# PowerManager.net
KiCad netlist of a schematic drawn in Altium Designer
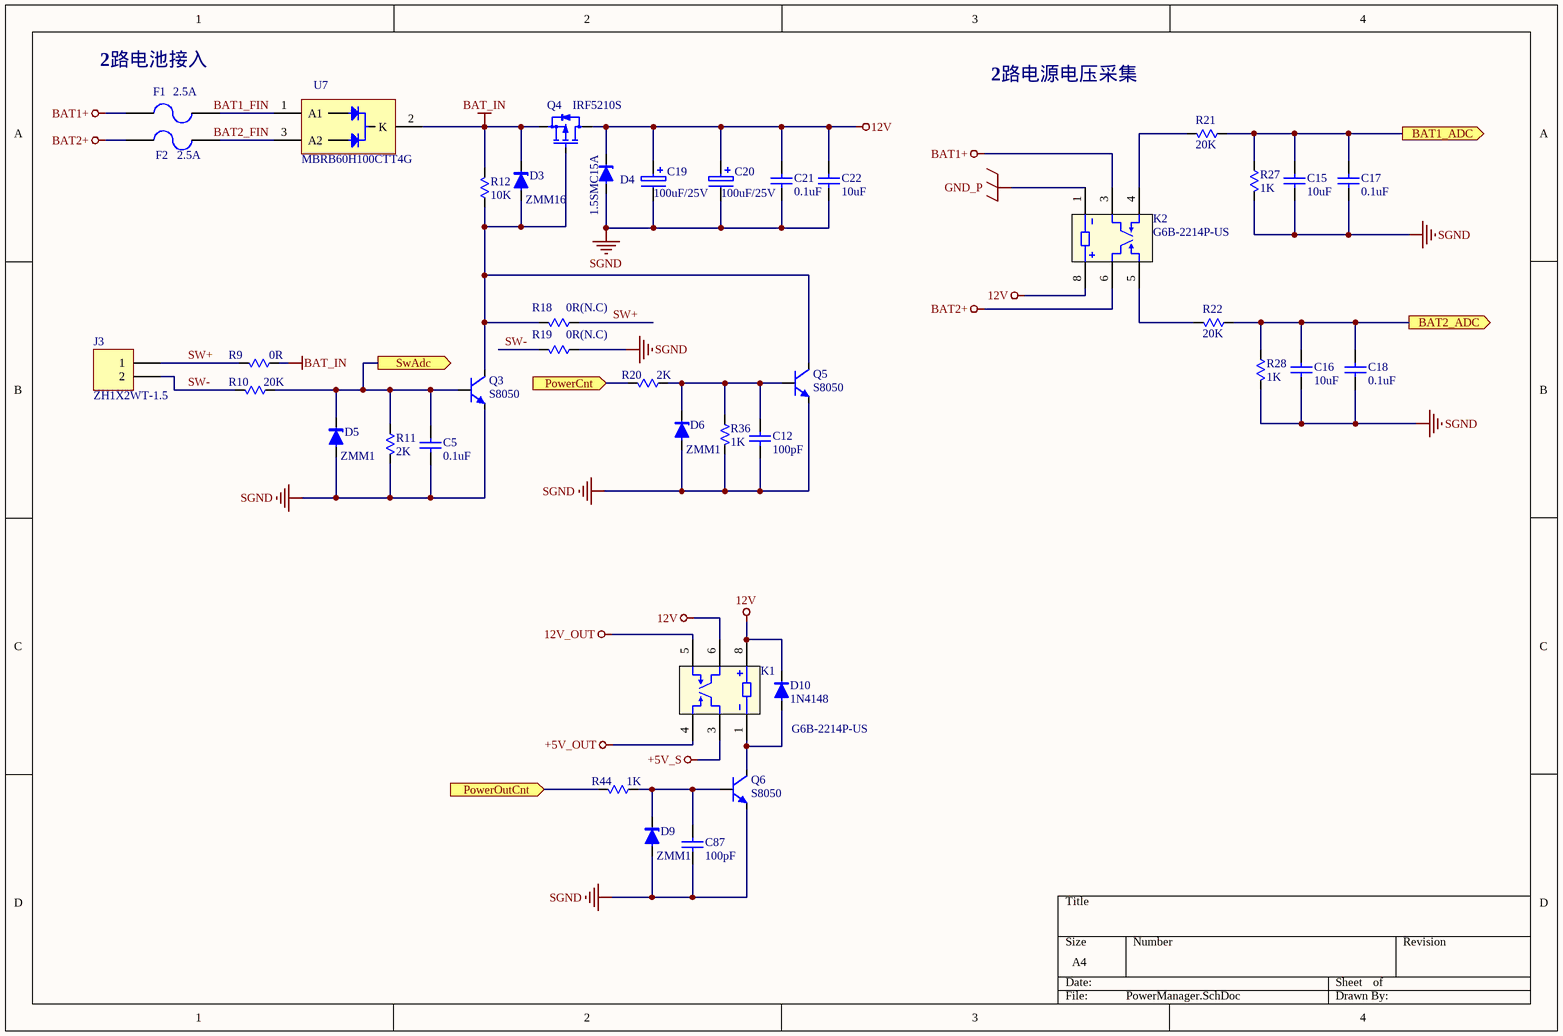
[diagram p0: PowerManager.SchDoc]

(export (version "E")
  (design (tool "Eeschema 10.0.6"))
  (components
    (comp (ref "C5")
      (value "0.1uF")
      (footprint "C0805")
      (description "Capacitor")
      (fields (field (name "PUBLISHER") "Altium Limited"))
      (libsource (lib "Miscellaneous Devices") (part "Cap"))
    )
    (comp (ref "C12")
      (value "100pF")
      (footprint "C0805")
      (description "Capacitor")
      (fields (field (name "PUBLISHER") "Altium Limited"))
      (libsource (lib "Miscellaneous Devices") (part "Cap"))
    )
    (comp (ref "C15")
      (value "10uF")
      (footprint "C0805")
      (description "CAP")
      (fields (field (name "PUBLISHER") "Altium Limited"))
      (libsource (lib "Passive Components Class") (part "CAP"))
    )
    (comp (ref "C16")
      (value "10uF")
      (footprint "C0805")
      (description "CAP")
      (fields (field (name "PUBLISHER") "Altium Limited"))
      (libsource (lib "Passive Components Class") (part "CAP"))
    )
    (comp (ref "C17")
      (value "0.1uF")
      (footprint "C0805")
      (description "CAP")
      (fields (field (name "PUBLISHER") "Altium Limited"))
      (libsource (lib "Passive Components Class") (part "CAP"))
    )
    (comp (ref "C18")
      (value "0.1uF")
      (footprint "C0805")
      (description "CAP")
      (fields (field (name "PUBLISHER") "Altium Limited"))
      (libsource (lib "Passive Components Class") (part "CAP"))
    )
    (comp (ref "C19")
      (value "100uF/25V")
      (footprint "CT7343-E-S")
      (description "Electrolytic Capacitor")
      (libsource (lib "*") (part "ELECTRO"))
    )
    (comp (ref "C20")
      (value "100uF/25V")
      (footprint "CT7343-E-S")
      (description "Electrolytic Capacitor")
      (libsource (lib "*") (part "ELECTRO"))
    )
    (comp (ref "C21")
      (value "0.1uF")
      (footprint "C0805")
      (description "Capacitor")
      (fields (field (name "PUBLISHER") "Altium Limited"))
      (libsource (lib "Miscellaneous Devices") (part "Cap"))
    )
    (comp (ref "C22")
      (value "10uF")
      (footprint "C0805")
      (description "Capacitor")
      (fields (field (name "PUBLISHER") "Altium Limited"))
      (libsource (lib "Miscellaneous Devices") (part "Cap"))
    )
    (comp (ref "C87")
      (value "100pF")
      (footprint "C0805")
      (description "Capacitor")
      (fields (field (name "PUBLISHER") "Altium Limited"))
      (libsource (lib "Miscellaneous Devices") (part "Cap"))
    )
    (comp (ref "D3")
      (value "ZMM16")
      (footprint "SOD-80")
      (description "Small Signal Zener Diodes")
      (libsource (lib "Passive Components Class") (part "DIODE-ZENER"))
    )
    (comp (ref "D4")
      (value "1.5SMC15A")
      (footprint "SMC")
      (description "Small Signal Zener Diodes")
      (libsource (lib "Passive Components Class") (part "DIODE-ZENER"))
    )
    (comp (ref "D5")
      (value "ZMM1")
      (footprint "SOD-80")
      (description "Small Signal Zener Diodes")
      (libsource (lib "Passive Components Class") (part "DIODE-ZENER"))
    )
    (comp (ref "D6")
      (value "ZMM1")
      (footprint "SOD-80")
      (description "Small Signal Zener Diodes")
      (libsource (lib "Passive Components Class") (part "DIODE-ZENER"))
    )
    (comp (ref "D9")
      (value "ZMM1")
      (footprint "SOD-80")
      (description "Small Signal Zener Diodes")
      (libsource (lib "Passive Components Class") (part "DIODE-ZENER"))
    )
    (comp (ref "D10")
      (value "1N4148")
      (footprint "SOD-80")
      (description "Silicon Epitaxial Planar Diodes")
      (libsource (lib "Passive Components Class") (part "DIODE-SWITCHING"))
    )
    (comp (ref "F1")
      (value "2.5A")
      (footprint "F1812")
      (description "Fuse")
      (libsource (lib "*") (part "FUSE2"))
    )
    (comp (ref "F2")
      (value "2.5A")
      (footprint "F1812")
      (description "Fuse")
      (libsource (lib "*") (part "FUSE2"))
    )
    (comp (ref "J3")
      (value "ZH1X2WT-1.5")
      (footprint "ZH1X2WT-1.5")
      (description "Header, 2-Pin")
      (fields (field (name "PUBLISHER") "Altium Limited"))
      (libsource (lib "Miscellaneous Connectors") (part "Header 2"))
    )
    (comp (ref "K1")
      (value "G6B-2214P-US")
      (footprint "G6B-2214P-Us")
      (libsource (lib "Passive Components Class") (part "G6B-2214P-US"))
    )
    (comp (ref "K2")
      (value "G6B-2214P-US")
      (footprint "G6B-2214P-Us")
      (libsource (lib "") (part "G6B-2214P-US_1"))
    )
    (comp (ref "Q3")
      (value "S8050")
      (footprint "SOT-23")
      (description "NPN General Purpose Amplifier")
      (fields (field (name "PUBLISHER") "Altium Limited"))
      (libsource (lib "Bdmc4810") (part "NPN"))
    )
    (comp (ref "Q4")
      (value "IRF5210S")
      (footprint "TO-262")
      (description "P-Channel 30-V (D-S), 150 C MOSFET")
      (libsource (lib "Passive Components Class") (part "PMOS"))
    )
    (comp (ref "Q5")
      (value "S8050")
      (footprint "SOT-23")
      (description "NPN General Purpose Amplifier")
      (fields (field (name "PUBLISHER") "Altium Limited"))
      (libsource (lib "Bdmc4810") (part "NPN"))
    )
    (comp (ref "Q6")
      (value "S8050")
      (footprint "SOT-23")
      (description "NPN General Purpose Amplifier")
      (fields (field (name "PUBLISHER") "Altium Limited"))
      (libsource (lib "Bdmc4810") (part "NPN"))
    )
    (comp (ref "R9")
      (value "0R")
      (footprint "R0805")
      (description "Resistor")
      (fields (field (name "PUBLISHER") "Altium Limited"))
      (libsource (lib "Temp") (part "Res"))
    )
    (comp (ref "R10")
      (value "20K")
      (footprint "R0805")
      (description "Resistor")
      (fields (field (name "PUBLISHER") "Altium Limited"))
      (libsource (lib "Temp") (part "Res"))
    )
    (comp (ref "R11")
      (value "2K")
      (footprint "R0805")
      (description "Resistor")
      (fields (field (name "PUBLISHER") "Altium Limited"))
      (libsource (lib "Temp") (part "Res"))
    )
    (comp (ref "R12")
      (value "10K")
      (footprint "R0805")
      (description "Resistor")
      (fields (field (name "PUBLISHER") "Altium Limited"))
      (libsource (lib "Temp") (part "Res"))
    )
    (comp (ref "R18")
      (value "0R(N.C)")
      (footprint "R0805")
      (description "Resistor")
      (fields (field (name "PUBLISHER") "Altium Limited"))
      (libsource (lib "") (part "RES_1"))
    )
    (comp (ref "R19")
      (value "0R(N.C)")
      (footprint "R0805")
      (description "Resistor")
      (fields (field (name "PUBLISHER") "Altium Limited"))
      (libsource (lib "") (part "RES_1"))
    )
    (comp (ref "R20")
      (value "2K")
      (footprint "R0805")
      (description "Resistor")
      (fields (field (name "PUBLISHER") "Altium Limited"))
      (libsource (lib "Temp") (part "Res"))
    )
    (comp (ref "R21")
      (value "20K")
      (footprint "R0805")
      (description "Resistor")
      (fields (field (name "PUBLISHER") "Altium Limited"))
      (libsource (lib "Passive Components Class") (part "RES"))
    )
    (comp (ref "R22")
      (value "20K")
      (footprint "R0805")
      (description "Resistor")
      (fields (field (name "PUBLISHER") "Altium Limited"))
      (libsource (lib "Passive Components Class") (part "RES"))
    )
    (comp (ref "R27")
      (value "1K")
      (footprint "R0805")
      (description "Resistor")
      (fields (field (name "PUBLISHER") "Altium Limited"))
      (libsource (lib "Passive Components Class") (part "RES"))
    )
    (comp (ref "R28")
      (value "1K")
      (footprint "R0805")
      (description "Resistor")
      (fields (field (name "PUBLISHER") "Altium Limited"))
      (libsource (lib "Passive Components Class") (part "RES"))
    )
    (comp (ref "R36")
      (value "1K")
      (footprint "R0805")
      (description "Resistor")
      (fields (field (name "PUBLISHER") "Altium Limited"))
      (libsource (lib "Temp") (part "Res"))
    )
    (comp (ref "R44")
      (value "1K")
      (footprint "R0805")
      (description "Resistor")
      (fields (field (name "PUBLISHER") "Altium Limited"))
      (libsource (lib "Temp") (part "Res"))
    )
    (comp (ref "U7")
      (value "MBRB60H100CTT4G")
      (footprint "TO-262")
      (libsource (lib "Logic Class") (part "VB30200C"))
    )
  )
  (nets
    (net (code "1") (name "+5V_OUT") (class "Default")
      (node (ref "K1") (pin "4") (pinfunction "4_4") (pintype "passive"))
    )
    (net (code "2") (name "+5V_S") (class "Default")
      (node (ref "K1") (pin "3") (pinfunction "3_3") (pintype "passive"))
    )
    (net (code "3") (name "/BAT1_ADC") (class "Default")
      (node (ref "C15") (pin "1") (pinfunction "1_1") (pintype "passive"))
      (node (ref "C17") (pin "1") (pinfunction "1_1") (pintype "passive"))
      (node (ref "R21") (pin "2") (pinfunction "2_2") (pintype "passive"))
      (node (ref "R27") (pin "2") (pinfunction "2_2") (pintype "passive"))
    )
    (net (code "5") (name "/BAT2_ADC") (class "Default")
      (node (ref "C16") (pin "1") (pinfunction "1_1") (pintype "passive"))
      (node (ref "C18") (pin "1") (pinfunction "1_1") (pintype "passive"))
      (node (ref "R22") (pin "2") (pinfunction "2_2") (pintype "passive"))
      (node (ref "R28") (pin "2") (pinfunction "2_2") (pintype "passive"))
    )
    (net (code "7") (name "/PowerCnt") (class "Default")
      (node (ref "R20") (pin "1") (pinfunction "1_1") (pintype "passive"))
    )
    (net (code "8") (name "/PowerOutCnt") (class "Default")
      (node (ref "R44") (pin "1") (pinfunction "1_1") (pintype "passive"))
    )
    (net (code "9") (name "/SW+") (class "Default")
      (node (ref "J3") (pin "1") (pinfunction "1_1") (pintype "passive"))
      (node (ref "R18") (pin "1") (pinfunction "1_1") (pintype "passive"))
      (node (ref "R9") (pin "1") (pinfunction "1_1") (pintype "passive"))
    )
    (net (code "10") (name "/SW-") (class "Default")
      (node (ref "J3") (pin "2") (pinfunction "2_2") (pintype "passive"))
      (node (ref "R10") (pin "1") (pinfunction "1_1") (pintype "passive"))
      (node (ref "R19") (pin "2") (pinfunction "2_2") (pintype "passive"))
    )
    (net (code "11") (name "/SwAdc") (class "Default")
      (node (ref "C5") (pin "2") (pinfunction "2_2") (pintype "passive"))
      (node (ref "D5") (pin "2") (pinfunction "K_2") (pintype "passive"))
      (node (ref "Q3") (pin "1") (pinfunction "B_1") (pintype "passive"))
      (node (ref "R10") (pin "2") (pinfunction "2_2") (pintype "passive"))
      (node (ref "R11") (pin "2") (pinfunction "2_2") (pintype "passive"))
    )
    (net (code "12") (name "12V") (class "Default")
      (node (ref "C19") (pin "1") (pinfunction "1_1") (pintype "passive"))
      (node (ref "C20") (pin "1") (pinfunction "1_1") (pintype "passive"))
      (node (ref "C21") (pin "2") (pinfunction "2_2") (pintype "passive"))
      (node (ref "C22") (pin "2") (pinfunction "2_2") (pintype "passive"))
      (node (ref "D10") (pin "2") (pinfunction "K_2") (pintype "passive"))
      (node (ref "D4") (pin "2") (pinfunction "K_2") (pintype "passive"))
      (node (ref "K1") (pin "6") (pinfunction "6_6") (pintype "passive"))
      (node (ref "K1") (pin "8") (pinfunction "8_8") (pintype "passive"))
      (node (ref "K2") (pin "8") (pinfunction "8_8") (pintype "passive"))
      (node (ref "Q4") (pin "2") (pinfunction "D_2") (pintype "passive"))
    )
    (net (code "13") (name "12V_OUT") (class "Default")
      (node (ref "K1") (pin "5") (pinfunction "5_5") (pintype "passive"))
    )
    (net (code "14") (name "BAT1+") (class "Default")
      (node (ref "F1") (pin "1") (pinfunction "1_1") (pintype "passive"))
      (node (ref "K2") (pin "3") (pinfunction "3_3") (pintype "passive"))
    )
    (net (code "15") (name "BAT2+") (class "Default")
      (node (ref "F2") (pin "1") (pinfunction "1_1") (pintype "passive"))
      (node (ref "K2") (pin "6") (pinfunction "6_6") (pintype "passive"))
    )
    (net (code "16") (name "BAT_IN") (class "Default")
      (node (ref "D3") (pin "2") (pinfunction "K_2") (pintype "passive"))
      (node (ref "Q4") (pin "3") (pinfunction "S_3") (pintype "passive"))
      (node (ref "R12") (pin "1") (pinfunction "1_1") (pintype "passive"))
      (node (ref "R9") (pin "2") (pinfunction "2_2") (pintype "passive"))
      (node (ref "U7") (pin "2") (pinfunction "K_2") (pintype "passive"))
    )
    (net (code "17") (name "GND_P") (class "Default")
      (node (ref "K2") (pin "1") (pinfunction "1_1") (pintype "passive"))
    )
    (net (code "18") (name "Net-(D3-A)") (class "Default")
      (node (ref "D3") (pin "1") (pinfunction "A_1") (pintype "passive"))
      (node (ref "Q3") (pin "3") (pinfunction "C_3") (pintype "passive"))
      (node (ref "Q4") (pin "1") (pinfunction "G_1") (pintype "passive"))
      (node (ref "Q5") (pin "3") (pinfunction "C_3") (pintype "passive"))
      (node (ref "R12") (pin "2") (pinfunction "2_2") (pintype "passive"))
      (node (ref "R18") (pin "2") (pinfunction "2_2") (pintype "passive"))
    )
    (net (code "19") (name "Net-(D6-K)") (class "Default")
      (node (ref "C12") (pin "2") (pinfunction "2_2") (pintype "passive"))
      (node (ref "D6") (pin "2") (pinfunction "K_2") (pintype "passive"))
      (node (ref "Q5") (pin "1") (pinfunction "B_1") (pintype "passive"))
      (node (ref "R20") (pin "2") (pinfunction "2_2") (pintype "passive"))
      (node (ref "R36") (pin "2") (pinfunction "2_2") (pintype "passive"))
    )
    (net (code "20") (name "Net-(D9-K)") (class "Default")
      (node (ref "C87") (pin "2") (pinfunction "2_2") (pintype "passive"))
      (node (ref "D9") (pin "2") (pinfunction "K_2") (pintype "passive"))
      (node (ref "Q6") (pin "1") (pinfunction "B_1") (pintype "passive"))
      (node (ref "R44") (pin "2") (pinfunction "2_2") (pintype "passive"))
    )
    (net (code "21") (name "Net-(D10-A)") (class "Default")
      (node (ref "D10") (pin "1") (pinfunction "A_1") (pintype "passive"))
      (node (ref "K1") (pin "1") (pinfunction "1_1") (pintype "passive"))
      (node (ref "Q6") (pin "3") (pinfunction "C_3") (pintype "passive"))
    )
    (net (code "22") (name "Net-(K2-Pad4)") (class "Default")
      (node (ref "K2") (pin "4") (pinfunction "4_4") (pintype "passive"))
      (node (ref "R21") (pin "1") (pinfunction "1_1") (pintype "passive"))
    )
    (net (code "23") (name "Net-(K2-Pad5)") (class "Default")
      (node (ref "K2") (pin "5") (pinfunction "5_5") (pintype "passive"))
      (node (ref "R22") (pin "1") (pinfunction "1_1") (pintype "passive"))
    )
    (net (code "24") (name "Net-(U7-A1)") (class "Default")
      (node (ref "F1") (pin "2") (pinfunction "2_2") (pintype "passive"))
      (node (ref "U7") (pin "1") (pinfunction "A1_1") (pintype "passive"))
    )
    (net (code "25") (name "Net-(U7-A2)") (class "Default")
      (node (ref "F2") (pin "2") (pinfunction "2_2") (pintype "passive"))
      (node (ref "U7") (pin "3") (pinfunction "A2_3") (pintype "passive"))
    )
    (net (code "26") (name "SGND") (class "Default")
      (node (ref "C12") (pin "1") (pinfunction "1_1") (pintype "passive"))
      (node (ref "C15") (pin "2") (pinfunction "2_2") (pintype "passive"))
      (node (ref "C16") (pin "2") (pinfunction "2_2") (pintype "passive"))
      (node (ref "C17") (pin "2") (pinfunction "2_2") (pintype "passive"))
      (node (ref "C18") (pin "2") (pinfunction "2_2") (pintype "passive"))
      (node (ref "C19") (pin "2") (pinfunction "2_2") (pintype "passive"))
      (node (ref "C20") (pin "2") (pinfunction "2_2") (pintype "passive"))
      (node (ref "C21") (pin "1") (pinfunction "1_1") (pintype "passive"))
      (node (ref "C22") (pin "1") (pinfunction "1_1") (pintype "passive"))
      (node (ref "C5") (pin "1") (pinfunction "1_1") (pintype "passive"))
      (node (ref "C87") (pin "1") (pinfunction "1_1") (pintype "passive"))
      (node (ref "D4") (pin "1") (pinfunction "A_1") (pintype "passive"))
      (node (ref "D5") (pin "1") (pinfunction "A_1") (pintype "passive"))
      (node (ref "D6") (pin "1") (pinfunction "A_1") (pintype "passive"))
      (node (ref "D9") (pin "1") (pinfunction "A_1") (pintype "passive"))
      (node (ref "Q3") (pin "2") (pinfunction "E_2") (pintype "passive"))
      (node (ref "Q5") (pin "2") (pinfunction "E_2") (pintype "passive"))
      (node (ref "Q6") (pin "2") (pinfunction "E_2") (pintype "passive"))
      (node (ref "R11") (pin "1") (pinfunction "1_1") (pintype "passive"))
      (node (ref "R19") (pin "1") (pinfunction "1_1") (pintype "passive"))
      (node (ref "R27") (pin "1") (pinfunction "1_1") (pintype "passive"))
      (node (ref "R28") (pin "1") (pinfunction "1_1") (pintype "passive"))
      (node (ref "R36") (pin "1") (pinfunction "1_1") (pintype "passive"))
    )
  )
)
